# L_A_jumper_bed.net
KiCad netlist of a schematic drawn in EAGLE
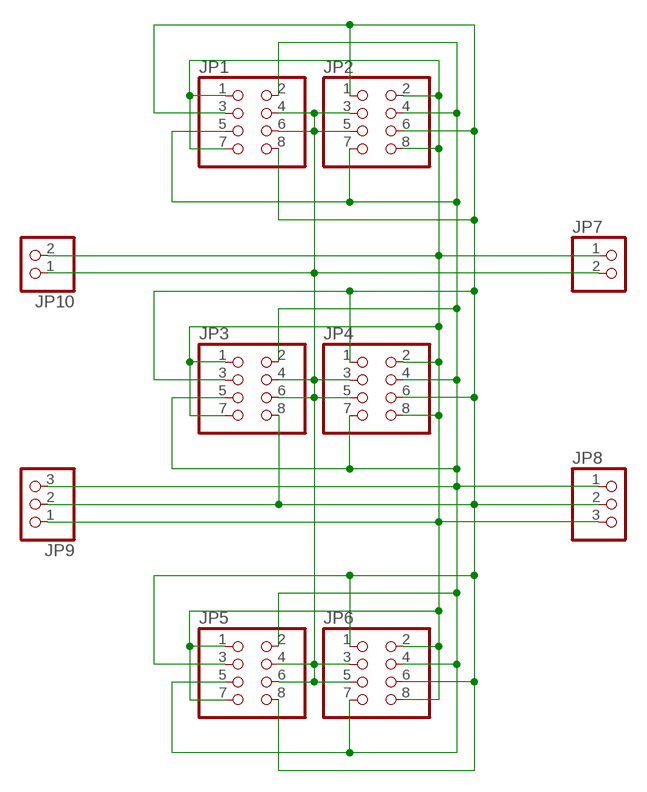
[diagram p0: schematic, sheet 1]

(export (version "E")
  (design (tool "Eeschema 10.0.6"))
  (components
    (comp (ref "JP1")
      (value "PINHD-2X4")
      (footprint "eagle-import:2X04")
      (libsource (lib "eagle-import") (part "PINHD-2X4"))
    )
    (comp (ref "JP2")
      (value "PINHD-2X4")
      (footprint "eagle-import:2X04")
      (libsource (lib "eagle-import") (part "PINHD-2X4"))
    )
    (comp (ref "JP3")
      (value "PINHD-2X4")
      (footprint "eagle-import:2X04")
      (libsource (lib "eagle-import") (part "PINHD-2X4"))
    )
    (comp (ref "JP4")
      (value "PINHD-2X4")
      (footprint "eagle-import:2X04")
      (libsource (lib "eagle-import") (part "PINHD-2X4"))
    )
    (comp (ref "JP5")
      (value "PINHD-2X4")
      (footprint "eagle-import:2X04")
      (libsource (lib "eagle-import") (part "PINHD-2X4"))
    )
    (comp (ref "JP6")
      (value "PINHD-2X4")
      (footprint "eagle-import:2X04")
      (libsource (lib "eagle-import") (part "PINHD-2X4"))
    )
    (comp (ref "JP7")
      (value "PINHD-1X2/90")
      (footprint "eagle-import:1X02_90")
      (libsource (lib "eagle-import") (part "PINHD-1X2/90"))
    )
    (comp (ref "JP8")
      (value "PINHD-1X3/90")
      (footprint "eagle-import:1X03_90")
      (libsource (lib "eagle-import") (part "PINHD-1X3/90"))
    )
    (comp (ref "JP9")
      (value "PINHD-1X31X03/90F")
      (footprint "eagle-import:1X03_90F")
      (libsource (lib "eagle-import") (part "PINHD-1X31X03/90F"))
    )
    (comp (ref "JP10")
      (value "PINHD-1X21X02/90F")
      (footprint "eagle-import:1X02_90F")
      (libsource (lib "eagle-import") (part "PINHD-1X21X02/90F"))
    )
  )
  (nets
    (net (code "1") (name "Net-(JP1-Pad1)") (class "Default")
      (node (ref "JP1") (pin "1") (pinfunction "1_1") (pintype "passive"))
      (node (ref "JP1") (pin "7") (pinfunction "7_7") (pintype "passive"))
      (node (ref "JP10") (pin "2") (pinfunction "2_2") (pintype "passive"))
      (node (ref "JP2") (pin "2") (pinfunction "2_2") (pintype "passive"))
      (node (ref "JP2") (pin "8") (pinfunction "8_8") (pintype "passive"))
      (node (ref "JP3") (pin "1") (pinfunction "1_1") (pintype "passive"))
      (node (ref "JP3") (pin "7") (pinfunction "7_7") (pintype "passive"))
      (node (ref "JP4") (pin "2") (pinfunction "2_2") (pintype "passive"))
      (node (ref "JP4") (pin "8") (pinfunction "8_8") (pintype "passive"))
      (node (ref "JP5") (pin "1") (pinfunction "1_1") (pintype "passive"))
      (node (ref "JP5") (pin "7") (pinfunction "7_7") (pintype "passive"))
      (node (ref "JP6") (pin "2") (pinfunction "2_2") (pintype "passive"))
      (node (ref "JP6") (pin "8") (pinfunction "8_8") (pintype "passive"))
      (node (ref "JP7") (pin "1") (pinfunction "1_1") (pintype "passive"))
      (node (ref "JP8") (pin "3") (pinfunction "3_3") (pintype "passive"))
      (node (ref "JP9") (pin "1") (pinfunction "1_1") (pintype "passive"))
    )
    (net (code "2") (name "Net-(JP1-Pad2)") (class "Default")
      (node (ref "JP1") (pin "2") (pinfunction "2_2") (pintype "passive"))
      (node (ref "JP1") (pin "5") (pinfunction "5_5") (pintype "passive"))
      (node (ref "JP2") (pin "4") (pinfunction "4_4") (pintype "passive"))
      (node (ref "JP2") (pin "7") (pinfunction "7_7") (pintype "passive"))
      (node (ref "JP3") (pin "2") (pinfunction "2_2") (pintype "passive"))
      (node (ref "JP3") (pin "5") (pinfunction "5_5") (pintype "passive"))
      (node (ref "JP4") (pin "4") (pinfunction "4_4") (pintype "passive"))
      (node (ref "JP4") (pin "7") (pinfunction "7_7") (pintype "passive"))
      (node (ref "JP5") (pin "2") (pinfunction "2_2") (pintype "passive"))
      (node (ref "JP5") (pin "5") (pinfunction "5_5") (pintype "passive"))
      (node (ref "JP6") (pin "4") (pinfunction "4_4") (pintype "passive"))
      (node (ref "JP6") (pin "7") (pinfunction "7_7") (pintype "passive"))
      (node (ref "JP8") (pin "1") (pinfunction "1_1") (pintype "passive"))
      (node (ref "JP9") (pin "3") (pinfunction "3_3") (pintype "passive"))
    )
    (net (code "3") (name "Net-(JP1-Pad3)") (class "Default")
      (node (ref "JP1") (pin "3") (pinfunction "3_3") (pintype "passive"))
      (node (ref "JP1") (pin "8") (pinfunction "8_8") (pintype "passive"))
      (node (ref "JP2") (pin "1") (pinfunction "1_1") (pintype "passive"))
      (node (ref "JP2") (pin "6") (pinfunction "6_6") (pintype "passive"))
      (node (ref "JP3") (pin "3") (pinfunction "3_3") (pintype "passive"))
      (node (ref "JP3") (pin "8") (pinfunction "8_8") (pintype "passive"))
      (node (ref "JP4") (pin "1") (pinfunction "1_1") (pintype "passive"))
      (node (ref "JP4") (pin "6") (pinfunction "6_6") (pintype "passive"))
      (node (ref "JP5") (pin "3") (pinfunction "3_3") (pintype "passive"))
      (node (ref "JP5") (pin "8") (pinfunction "8_8") (pintype "passive"))
      (node (ref "JP6") (pin "1") (pinfunction "1_1") (pintype "passive"))
      (node (ref "JP6") (pin "6") (pinfunction "6_6") (pintype "passive"))
      (node (ref "JP8") (pin "2") (pinfunction "2_2") (pintype "passive"))
      (node (ref "JP9") (pin "2") (pinfunction "2_2") (pintype "passive"))
    )
    (net (code "4") (name "Net-(JP1-Pad4)") (class "Default")
      (node (ref "JP1") (pin "4") (pinfunction "4_4") (pintype "passive"))
      (node (ref "JP1") (pin "6") (pinfunction "6_6") (pintype "passive"))
      (node (ref "JP10") (pin "1") (pinfunction "1_1") (pintype "passive"))
      (node (ref "JP2") (pin "3") (pinfunction "3_3") (pintype "passive"))
      (node (ref "JP2") (pin "5") (pinfunction "5_5") (pintype "passive"))
      (node (ref "JP3") (pin "4") (pinfunction "4_4") (pintype "passive"))
      (node (ref "JP3") (pin "6") (pinfunction "6_6") (pintype "passive"))
      (node (ref "JP4") (pin "3") (pinfunction "3_3") (pintype "passive"))
      (node (ref "JP4") (pin "5") (pinfunction "5_5") (pintype "passive"))
      (node (ref "JP5") (pin "4") (pinfunction "4_4") (pintype "passive"))
      (node (ref "JP5") (pin "6") (pinfunction "6_6") (pintype "passive"))
      (node (ref "JP6") (pin "3") (pinfunction "3_3") (pintype "passive"))
      (node (ref "JP6") (pin "5") (pinfunction "5_5") (pintype "passive"))
      (node (ref "JP7") (pin "2") (pinfunction "2_2") (pintype "passive"))
    )
  )
)
